# TPS92638_-_Breakoutv1_3.net
KiCad netlist of a schematic drawn in EAGLE
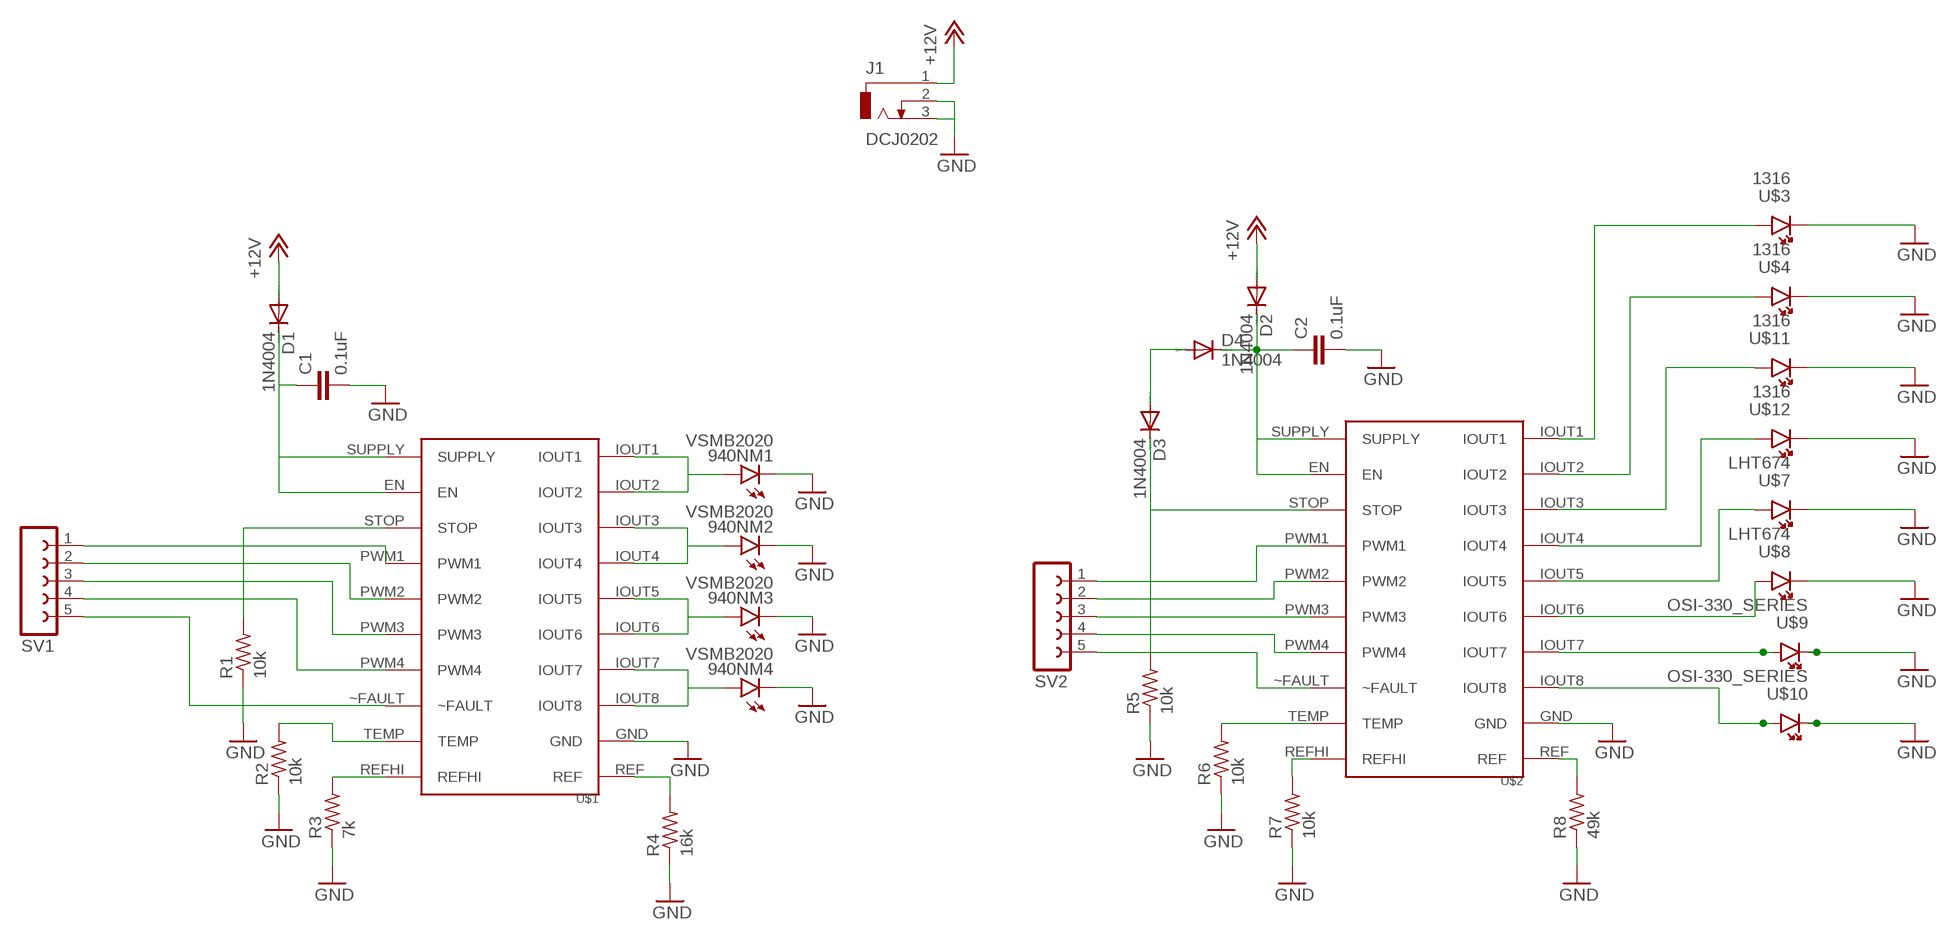
[diagram p0: schematic, sheet 1]

(export (version "E")
  (design (tool "Eeschema 10.0.6"))
  (components
    (comp (ref "940NM1")
      (value "VSMB2020")
      (footprint "eagle-import:GULLWING-2.3MM")
      (libsource (lib "eagle-import") (part "VSMB2020"))
    )
    (comp (ref "940NM2")
      (value "VSMB2020")
      (footprint "eagle-import:GULLWING-2.3MM")
      (libsource (lib "eagle-import") (part "VSMB2020"))
    )
    (comp (ref "940NM3")
      (value "VSMB2020")
      (footprint "eagle-import:GULLWING-2.3MM")
      (libsource (lib "eagle-import") (part "VSMB2020"))
    )
    (comp (ref "940NM4")
      (value "VSMB2020")
      (footprint "eagle-import:GULLWING-2.3MM")
      (libsource (lib "eagle-import") (part "VSMB2020"))
    )
    (comp (ref "C1")
      (value "0.1uF")
      (footprint "eagle-import:CAP")
      (libsource (lib "eagle-import") (part "CAP"))
    )
    (comp (ref "C2")
      (value "0.1uF")
      (footprint "eagle-import:CAP")
      (libsource (lib "eagle-import") (part "CAP"))
    )
    (comp (ref "D1")
      (value "1N4004")
      (footprint "eagle-import:DO35-7")
      (libsource (lib "eagle-import") (part "1N4148DO35-7"))
    )
    (comp (ref "D2")
      (value "1N4004")
      (footprint "eagle-import:DO35-7")
      (libsource (lib "eagle-import") (part "1N4148DO35-7"))
    )
    (comp (ref "D3")
      (value "1N4004")
      (footprint "eagle-import:DO35-7")
      (libsource (lib "eagle-import") (part "1N4148DO35-7"))
    )
    (comp (ref "D4")
      (value "1N4004")
      (footprint "eagle-import:DO35-7")
      (libsource (lib "eagle-import") (part "1N4148DO35-7"))
    )
    (comp (ref "J1")
      (value "DCJ0202")
      (footprint "eagle-import:DCJ0202")
      (libsource (lib "eagle-import") (part "DCJ0202"))
    )
    (comp (ref "R1")
      (value "10k")
      (footprint "eagle-import:LED")
      (libsource (lib "eagle-import") (part "LED"))
    )
    (comp (ref "R2")
      (value "10k")
      (footprint "eagle-import:LED")
      (libsource (lib "eagle-import") (part "LED"))
    )
    (comp (ref "R3")
      (value "7k")
      (footprint "eagle-import:LED")
      (libsource (lib "eagle-import") (part "LED"))
    )
    (comp (ref "R4")
      (value "16k")
      (footprint "eagle-import:LED")
      (libsource (lib "eagle-import") (part "LED"))
    )
    (comp (ref "R5")
      (value "10k")
      (footprint "eagle-import:LED")
      (libsource (lib "eagle-import") (part "LED"))
    )
    (comp (ref "R6")
      (value "10k")
      (footprint "eagle-import:LED")
      (libsource (lib "eagle-import") (part "LED"))
    )
    (comp (ref "R7")
      (value "10k")
      (footprint "eagle-import:LED")
      (libsource (lib "eagle-import") (part "LED"))
    )
    (comp (ref "R8")
      (value "49k")
      (footprint "eagle-import:LED")
      (libsource (lib "eagle-import") (part "LED"))
    )
    (comp (ref "SV1")
      (value "FE05-1")
      (footprint "eagle-import:FE05-1")
      (libsource (lib "eagle-import") (part "FE05-1"))
    )
    (comp (ref "SV2")
      (value "FE05-1")
      (footprint "eagle-import:FE05-1")
      (libsource (lib "eagle-import") (part "FE05-1"))
    )
    (comp (ref "U$1")
      (value "TPS92638")
      (footprint "eagle-import:TPS92638")
      (libsource (lib "eagle-import") (part "TPS92638"))
    )
    (comp (ref "U$2")
      (value "TPS92638")
      (footprint "eagle-import:TPS92638")
      (libsource (lib "eagle-import") (part "TPS92638"))
    )
    (comp (ref "U$3")
      (value "1316")
      (footprint "eagle-import:1316")
      (libsource (lib "eagle-import") (part "1316"))
    )
    (comp (ref "U$4")
      (value "1316")
      (footprint "eagle-import:1316")
      (libsource (lib "eagle-import") (part "1316"))
    )
    (comp (ref "U$7")
      (value "LHT674")
      (footprint "eagle-import:LHT674")
      (libsource (lib "eagle-import") (part "LHT674"))
    )
    (comp (ref "U$8")
      (value "LHT674")
      (footprint "eagle-import:LHT674")
      (libsource (lib "eagle-import") (part "LHT674"))
    )
    (comp (ref "U$9")
      (value "OSI-330_SERIES")
      (footprint "eagle-import:OSI-330_SERIES")
      (libsource (lib "eagle-import") (part "OSI-330_SERIES"))
    )
    (comp (ref "U$10")
      (value "OSI-330_SERIES")
      (footprint "eagle-import:OSI-330_SERIES")
      (libsource (lib "eagle-import") (part "OSI-330_SERIES"))
    )
    (comp (ref "U$11")
      (value "1316")
      (footprint "eagle-import:1316")
      (libsource (lib "eagle-import") (part "1316"))
    )
    (comp (ref "U$12")
      (value "1316")
      (footprint "eagle-import:1316")
      (libsource (lib "eagle-import") (part "1316"))
    )
  )
  (nets
    (net (code "1") (name "+12V") (class "Default")
      (node (ref "D1") (pin "A") (pinfunction "A_A") (pintype "passive"))
      (node (ref "D2") (pin "A") (pinfunction "A_A") (pintype "passive"))
      (node (ref "J1") (pin "1") (pinfunction "1_1") (pintype "passive"))
    )
    (net (code "2") (name "GND") (class "Default")
      (node (ref "940NM1") (pin "P$2") (pinfunction "C_P$2") (pintype "passive"))
      (node (ref "940NM2") (pin "P$2") (pinfunction "C_P$2") (pintype "passive"))
      (node (ref "940NM3") (pin "P$2") (pinfunction "C_P$2") (pintype "passive"))
      (node (ref "940NM4") (pin "P$2") (pinfunction "C_P$2") (pintype "passive"))
      (node (ref "C1") (pin "2") (pinfunction "2_2") (pintype "passive"))
      (node (ref "C2") (pin "2") (pinfunction "2_2") (pintype "passive"))
      (node (ref "J1") (pin "2") (pinfunction "2_2") (pintype "passive"))
      (node (ref "J1") (pin "3") (pinfunction "3_3") (pintype "passive"))
      (node (ref "R1") (pin "1") (pinfunction "1_1") (pintype "passive"))
      (node (ref "R2") (pin "1") (pinfunction "1_1") (pintype "passive"))
      (node (ref "R3") (pin "1") (pinfunction "1_1") (pintype "passive"))
      (node (ref "R4") (pin "1") (pinfunction "1_1") (pintype "passive"))
      (node (ref "R5") (pin "1") (pinfunction "1_1") (pintype "passive"))
      (node (ref "R6") (pin "1") (pinfunction "1_1") (pintype "passive"))
      (node (ref "R7") (pin "1") (pinfunction "1_1") (pintype "passive"))
      (node (ref "R8") (pin "1") (pinfunction "1_1") (pintype "passive"))
      (node (ref "U$1") (pin "GND") (pinfunction "GND_GND") (pintype "bidirectional"))
      (node (ref "U$10") (pin "CATHODE") (pinfunction "P$1_CATHODE") (pintype "passive"))
      (node (ref "U$11") (pin "CATHODE") (pinfunction "CATHODE_CATHODE") (pintype "passive"))
      (node (ref "U$12") (pin "CATHODE") (pinfunction "CATHODE_CATHODE") (pintype "passive"))
      (node (ref "U$2") (pin "GND") (pinfunction "GND_GND") (pintype "bidirectional"))
      (node (ref "U$3") (pin "CATHODE") (pinfunction "CATHODE_CATHODE") (pintype "passive"))
      (node (ref "U$4") (pin "CATHODE") (pinfunction "CATHODE_CATHODE") (pintype "passive"))
      (node (ref "U$7") (pin "CATHODE") (pinfunction "CATHODE_CATHODE") (pintype "passive"))
      (node (ref "U$8") (pin "CATHODE") (pinfunction "CATHODE_CATHODE") (pintype "passive"))
      (node (ref "U$9") (pin "CATHODE") (pinfunction "P$1_CATHODE") (pintype "passive"))
    )
    (net (code "3") (name "Net-(940NM1-A)") (class "Default")
      (node (ref "940NM1") (pin "P$1") (pinfunction "A_P$1") (pintype "passive"))
      (node (ref "U$1") (pin "IOUT1") (pinfunction "IOUT1_IOUT1") (pintype "bidirectional"))
      (node (ref "U$1") (pin "IOUT2") (pinfunction "IOUT2_IOUT2") (pintype "bidirectional"))
    )
    (net (code "4") (name "Net-(940NM2-A)") (class "Default")
      (node (ref "940NM2") (pin "P$1") (pinfunction "A_P$1") (pintype "passive"))
      (node (ref "U$1") (pin "IOUT3") (pinfunction "IOUT3_IOUT3") (pintype "bidirectional"))
      (node (ref "U$1") (pin "IOUT4") (pinfunction "IOUT4_IOUT4") (pintype "bidirectional"))
    )
    (net (code "5") (name "Net-(940NM3-A)") (class "Default")
      (node (ref "940NM3") (pin "P$1") (pinfunction "A_P$1") (pintype "passive"))
      (node (ref "U$1") (pin "IOUT5") (pinfunction "IOUT5_IOUT5") (pintype "bidirectional"))
      (node (ref "U$1") (pin "IOUT6") (pinfunction "IOUT6_IOUT6") (pintype "bidirectional"))
    )
    (net (code "6") (name "Net-(940NM4-A)") (class "Default")
      (node (ref "940NM4") (pin "P$1") (pinfunction "A_P$1") (pintype "passive"))
      (node (ref "U$1") (pin "IOUT7") (pinfunction "IOUT7_IOUT7") (pintype "bidirectional"))
      (node (ref "U$1") (pin "IOUT8") (pinfunction "IOUT8_IOUT8") (pintype "bidirectional"))
    )
    (net (code "7") (name "Net-(C1-Pad1)") (class "Default")
      (node (ref "C1") (pin "1") (pinfunction "1_1") (pintype "passive"))
      (node (ref "D1") (pin "C") (pinfunction "C_C") (pintype "passive"))
      (node (ref "U$1") (pin "EN") (pinfunction "EN_EN") (pintype "bidirectional"))
      (node (ref "U$1") (pin "SUPPLY") (pinfunction "SUPPLY_SUPPLY") (pintype "bidirectional"))
    )
    (net (code "8") (name "Net-(C2-Pad1)") (class "Default")
      (node (ref "C2") (pin "1") (pinfunction "1_1") (pintype "passive"))
      (node (ref "D2") (pin "C") (pinfunction "C_C") (pintype "passive"))
      (node (ref "D4") (pin "C") (pinfunction "C_C") (pintype "passive"))
      (node (ref "U$2") (pin "EN") (pinfunction "EN_EN") (pintype "bidirectional"))
      (node (ref "U$2") (pin "SUPPLY") (pinfunction "SUPPLY_SUPPLY") (pintype "bidirectional"))
    )
    (net (code "9") (name "Net-(D3-PadA)") (class "Default")
      (node (ref "D3") (pin "A") (pinfunction "A_A") (pintype "passive"))
      (node (ref "D4") (pin "A") (pinfunction "A_A") (pintype "passive"))
    )
    (net (code "10") (name "Net-(D3-PadC)") (class "Default")
      (node (ref "D3") (pin "C") (pinfunction "C_C") (pintype "passive"))
      (node (ref "R5") (pin "2") (pinfunction "2_2") (pintype "passive"))
      (node (ref "U$2") (pin "STOP") (pinfunction "STOP_STOP") (pintype "bidirectional"))
    )
    (net (code "11") (name "Net-(R1-Pad2)") (class "Default")
      (node (ref "R1") (pin "2") (pinfunction "2_2") (pintype "passive"))
      (node (ref "U$1") (pin "STOP") (pinfunction "STOP_STOP") (pintype "bidirectional"))
    )
    (net (code "12") (name "Net-(R2-Pad2)") (class "Default")
      (node (ref "R2") (pin "2") (pinfunction "2_2") (pintype "passive"))
      (node (ref "U$1") (pin "TEMP") (pinfunction "TEMP_TEMP") (pintype "bidirectional"))
    )
    (net (code "13") (name "Net-(R3-Pad2)") (class "Default")
      (node (ref "R3") (pin "2") (pinfunction "2_2") (pintype "passive"))
      (node (ref "U$1") (pin "REFHI") (pinfunction "REFHI_REFHI") (pintype "bidirectional"))
    )
    (net (code "14") (name "Net-(R4-Pad2)") (class "Default")
      (node (ref "R4") (pin "2") (pinfunction "2_2") (pintype "passive"))
      (node (ref "U$1") (pin "REF") (pinfunction "REF_REF") (pintype "bidirectional"))
    )
    (net (code "15") (name "Net-(R6-Pad2)") (class "Default")
      (node (ref "R6") (pin "2") (pinfunction "2_2") (pintype "passive"))
      (node (ref "U$2") (pin "TEMP") (pinfunction "TEMP_TEMP") (pintype "bidirectional"))
    )
    (net (code "16") (name "Net-(R7-Pad2)") (class "Default")
      (node (ref "R7") (pin "2") (pinfunction "2_2") (pintype "passive"))
      (node (ref "U$2") (pin "REFHI") (pinfunction "REFHI_REFHI") (pintype "bidirectional"))
    )
    (net (code "17") (name "Net-(R8-Pad2)") (class "Default")
      (node (ref "R8") (pin "2") (pinfunction "2_2") (pintype "passive"))
      (node (ref "U$2") (pin "REF") (pinfunction "REF_REF") (pintype "bidirectional"))
    )
    (net (code "18") (name "Net-(SV1-Pad1)") (class "Default")
      (node (ref "SV1") (pin "1") (pinfunction "1_1") (pintype "passive"))
      (node (ref "U$1") (pin "PWM1") (pinfunction "PWM1_PWM1") (pintype "bidirectional"))
    )
    (net (code "19") (name "Net-(SV1-Pad2)") (class "Default")
      (node (ref "SV1") (pin "2") (pinfunction "2_2") (pintype "passive"))
      (node (ref "U$1") (pin "PWM2") (pinfunction "PWM2_PWM2") (pintype "bidirectional"))
    )
    (net (code "20") (name "Net-(SV1-Pad3)") (class "Default")
      (node (ref "SV1") (pin "3") (pinfunction "3_3") (pintype "passive"))
      (node (ref "U$1") (pin "PWM3") (pinfunction "PWM3_PWM3") (pintype "bidirectional"))
    )
    (net (code "21") (name "Net-(SV1-Pad4)") (class "Default")
      (node (ref "SV1") (pin "4") (pinfunction "4_4") (pintype "passive"))
      (node (ref "U$1") (pin "PWM4") (pinfunction "PWM4_PWM4") (pintype "bidirectional"))
    )
    (net (code "22") (name "Net-(SV2-Pad1)") (class "Default")
      (node (ref "SV2") (pin "1") (pinfunction "1_1") (pintype "passive"))
      (node (ref "U$2") (pin "PWM1") (pinfunction "PWM1_PWM1") (pintype "bidirectional"))
    )
    (net (code "23") (name "Net-(SV2-Pad2)") (class "Default")
      (node (ref "SV2") (pin "2") (pinfunction "2_2") (pintype "passive"))
      (node (ref "U$2") (pin "PWM2") (pinfunction "PWM2_PWM2") (pintype "bidirectional"))
    )
    (net (code "24") (name "Net-(SV2-Pad3)") (class "Default")
      (node (ref "SV2") (pin "3") (pinfunction "3_3") (pintype "passive"))
      (node (ref "U$2") (pin "PWM3") (pinfunction "PWM3_PWM3") (pintype "bidirectional"))
    )
    (net (code "25") (name "Net-(SV2-Pad4)") (class "Default")
      (node (ref "SV2") (pin "4") (pinfunction "4_4") (pintype "passive"))
      (node (ref "U$2") (pin "PWM4") (pinfunction "PWM4_PWM4") (pintype "bidirectional"))
    )
    (net (code "26") (name "Net-(U$1-~{FAULT})") (class "Default")
      (node (ref "SV1") (pin "5") (pinfunction "5_5") (pintype "passive"))
      (node (ref "U$1") (pin "~FAULT") (pinfunction "~{FAULT}_~FAULT") (pintype "bidirectional"))
    )
    (net (code "27") (name "Net-(U$2-PadIOUT1)") (class "Default")
      (node (ref "U$2") (pin "IOUT1") (pinfunction "IOUT1_IOUT1") (pintype "bidirectional"))
      (node (ref "U$3") (pin "ANODE") (pinfunction "ANODE_ANODE") (pintype "passive"))
    )
    (net (code "28") (name "Net-(U$2-PadIOUT2)") (class "Default")
      (node (ref "U$2") (pin "IOUT2") (pinfunction "IOUT2_IOUT2") (pintype "bidirectional"))
      (node (ref "U$4") (pin "ANODE") (pinfunction "ANODE_ANODE") (pintype "passive"))
    )
    (net (code "29") (name "Net-(U$2-PadIOUT5)") (class "Default")
      (node (ref "U$2") (pin "IOUT5") (pinfunction "IOUT5_IOUT5") (pintype "bidirectional"))
      (node (ref "U$7") (pin "ANODE") (pinfunction "ANODE_ANODE") (pintype "passive"))
    )
    (net (code "30") (name "Net-(U$2-PadIOUT6)") (class "Default")
      (node (ref "U$2") (pin "IOUT6") (pinfunction "IOUT6_IOUT6") (pintype "bidirectional"))
      (node (ref "U$8") (pin "ANODE") (pinfunction "ANODE_ANODE") (pintype "passive"))
    )
    (net (code "31") (name "Net-(U$2-PadIOUT7)") (class "Default")
      (node (ref "U$2") (pin "IOUT7") (pinfunction "IOUT7_IOUT7") (pintype "bidirectional"))
      (node (ref "U$9") (pin "ANODE") (pinfunction "ANODE_ANODE") (pintype "passive"))
    )
    (net (code "32") (name "Net-(U$2-~{FAULT})") (class "Default")
      (node (ref "SV2") (pin "5") (pinfunction "5_5") (pintype "passive"))
      (node (ref "U$2") (pin "~FAULT") (pinfunction "~{FAULT}_~FAULT") (pintype "bidirectional"))
    )
    (net (code "33") (name "Net-(U$10-PadANODE)") (class "Default")
      (node (ref "U$10") (pin "ANODE") (pinfunction "ANODE_ANODE") (pintype "passive"))
      (node (ref "U$2") (pin "IOUT8") (pinfunction "IOUT8_IOUT8") (pintype "bidirectional"))
    )
    (net (code "34") (name "Net-(U$11-PadANODE)") (class "Default")
      (node (ref "U$11") (pin "ANODE") (pinfunction "ANODE_ANODE") (pintype "passive"))
      (node (ref "U$2") (pin "IOUT3") (pinfunction "IOUT3_IOUT3") (pintype "bidirectional"))
    )
    (net (code "35") (name "Net-(U$12-PadANODE)") (class "Default")
      (node (ref "U$12") (pin "ANODE") (pinfunction "ANODE_ANODE") (pintype "passive"))
      (node (ref "U$2") (pin "IOUT4") (pinfunction "IOUT4_IOUT4") (pintype "bidirectional"))
    )
  )
)
